# plug-v24-Make-board-myself-to-test-circu.net
KiCad netlist of a schematic drawn in EAGLE
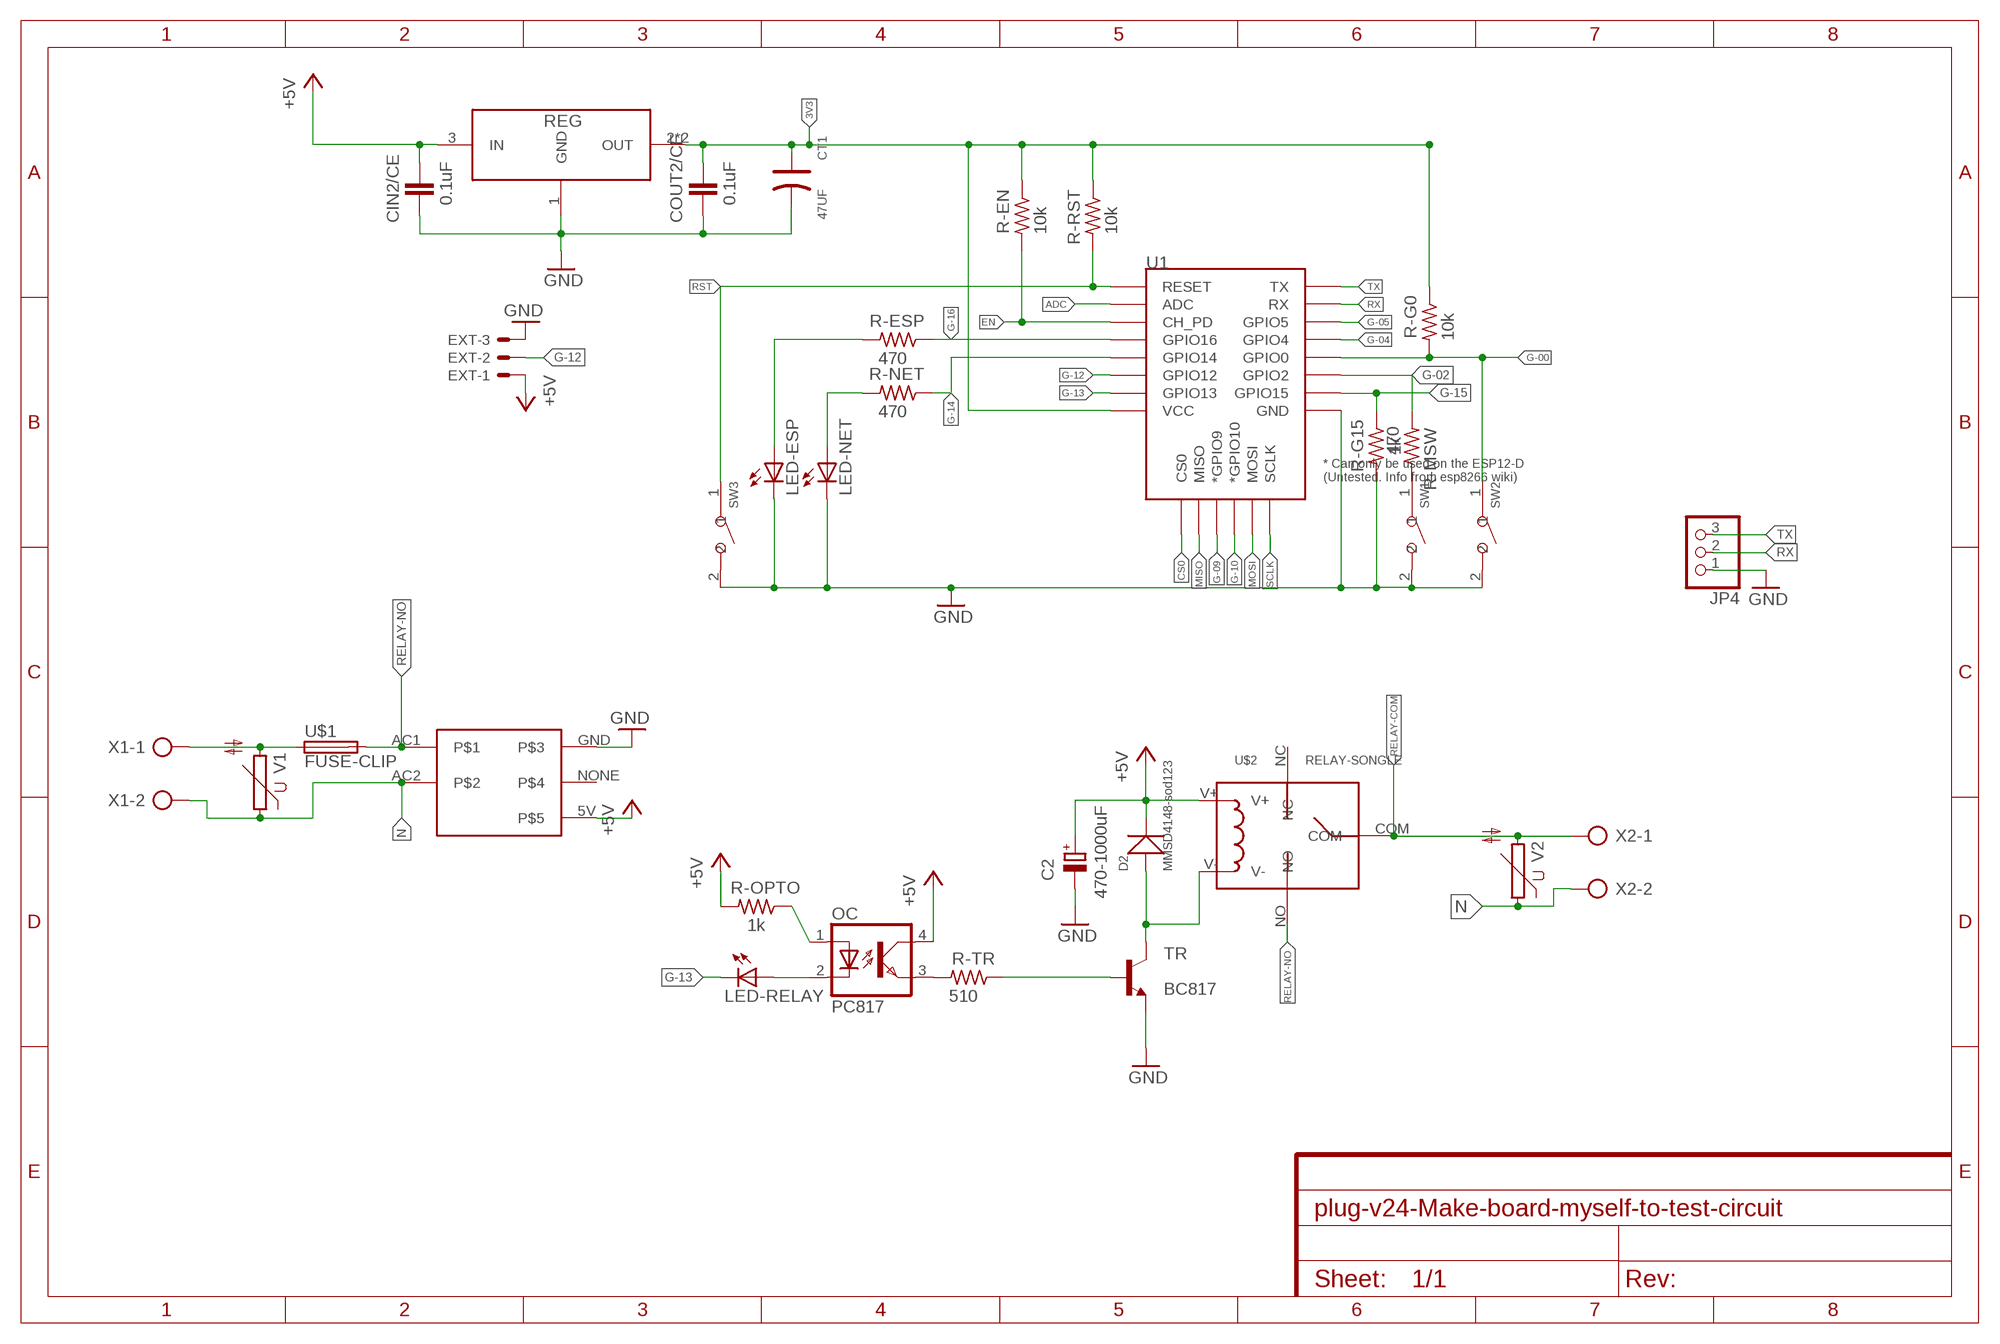
[diagram p0: schematic, sheet 1]

(export (version "E")
  (design (tool "Eeschema 10.0.6"))
  (components
    (comp (ref "C2")
      (value "470-1000uF")
      (footprint "eagle-import:E3,5-8")
      (libsource (lib "eagle-import") (part "CPOL-EUE3.5-8"))
    )
    (comp (ref "CIN2/CE")
      (value "0.1uF")
      (footprint "eagle-import:C0805K")
      (libsource (lib "eagle-import") (part "C-EUC0805K"))
    )
    (comp (ref "COUT2/CE")
      (value "0.1uF")
      (footprint "eagle-import:C0805K")
      (libsource (lib "eagle-import") (part "C-EUC0805K"))
    )
    (comp (ref "CT1")
      (value "47UF")
      (footprint "eagle-import:ELECTRO-SMD-C-6MM")
      (fields (field (name "MPN") "CS1E470M-CRE54"))
      (libsource (lib "eagle-import") (part "ALUMINUM-SMD-47UF-25V(D6.3-H5.3MM)"))
    )
    (comp (ref "D2")
      (value "MMSD4148-sod123")
      (footprint "eagle-import:SOD-123")
      (fields (field (name "MPN") "MMSD4148"))
      (libsource (lib "eagle-import") (part "SMD-DIODE-100V-200MA(SOD-123)"))
    )
    (comp (ref "EXT")
      (value "53048-03")
      (footprint "eagle-import:53048-03")
      (fields (field (name "MF") "WALDOM/MOLEX") (field (name "MPN") "53048-0310"))
      (libsource (lib "eagle-import") (part "53?-03048"))
    )
    (comp (ref "JP4")
      (value "PINHD-1X3")
      (footprint "eagle-import:1X03")
      (libsource (lib "eagle-import") (part "PINHD-1X3"))
    )
    (comp (ref "LED-ESP")
      (value "LEDCHIPLED_0805")
      (footprint "eagle-import:CHIPLED_0805")
      (libsource (lib "eagle-import") (part "LEDCHIPLED_0805"))
    )
    (comp (ref "LED-NET")
      (value "LEDCHIPLED_0805")
      (footprint "eagle-import:CHIPLED_0805")
      (libsource (lib "eagle-import") (part "LEDCHIPLED_0805"))
    )
    (comp (ref "LED-RELAY")
      (value "LEDCHIPLED_0805")
      (footprint "eagle-import:CHIPLED_0805")
      (libsource (lib "eagle-import") (part "LEDCHIPLED_0805"))
    )
    (comp (ref "OC")
      (value "PC817")
      (footprint "eagle-import:DIL04")
      (fields (field (name "MPN") "PC817X4J000F"))
      (libsource (lib "eagle-import") (part "PC817"))
    )
    (comp (ref "R-EN")
      (value "10k")
      (footprint "eagle-import:M0805")
      (libsource (lib "eagle-import") (part "R-US_M0805"))
    )
    (comp (ref "R-ESP")
      (value "470")
      (footprint "eagle-import:M0805")
      (libsource (lib "eagle-import") (part "R-US_M0805"))
    )
    (comp (ref "R-G0")
      (value "10k")
      (footprint "eagle-import:M0805")
      (libsource (lib "eagle-import") (part "R-US_M0805"))
    )
    (comp (ref "R-G15")
      (value "1k")
      (footprint "eagle-import:M0805")
      (libsource (lib "eagle-import") (part "R-US_M0805"))
    )
    (comp (ref "R-MSW")
      (value "470")
      (footprint "eagle-import:M0805")
      (libsource (lib "eagle-import") (part "R-US_M0805"))
    )
    (comp (ref "R-NET")
      (value "470")
      (footprint "eagle-import:M0805")
      (libsource (lib "eagle-import") (part "R-US_M0805"))
    )
    (comp (ref "R-OPTO")
      (value "1k")
      (footprint "eagle-import:M0805")
      (libsource (lib "eagle-import") (part "R-US_M0805"))
    )
    (comp (ref "R-RST")
      (value "10k")
      (footprint "eagle-import:M0805")
      (libsource (lib "eagle-import") (part "R-US_M0805"))
    )
    (comp (ref "R-TR")
      (value "510")
      (footprint "eagle-import:M0805")
      (libsource (lib "eagle-import") (part "R-US_M0805"))
    )
    (comp (ref "REG")
      (value "AMS1117-3.3")
      (footprint "eagle-import:SOT-223")
      (libsource (lib "eagle-import") (part "AMS1117-3.3"))
    )
    (comp (ref "SW1")
      (value "DIP-BUTTON(2P-6.0X3.0X4.3MM)-TS-1101F")
      (footprint "eagle-import:SW2-5.0-6.0X3.0X4.3MM")
      (libsource (lib "eagle-import") (part "DIP-BUTTON(2P-6.0X3.0X4.3MM)-TS-1101F"))
    )
    (comp (ref "SW2")
      (value "DIP-BUTTON(2P-6.0X3.0X4.3MM)-TS-1101F")
      (footprint "eagle-import:SW2-5.0-6.0X3.0X4.3MM")
      (libsource (lib "eagle-import") (part "DIP-BUTTON(2P-6.0X3.0X4.3MM)-TS-1101F"))
    )
    (comp (ref "SW3")
      (value "DIP-BUTTON(2P-6.0X3.0X4.3MM)-TS-1101F")
      (footprint "eagle-import:SW2-5.0-6.0X3.0X4.3MM")
      (libsource (lib "eagle-import") (part "DIP-BUTTON(2P-6.0X3.0X4.3MM)-TS-1101F"))
    )
    (comp (ref "TR")
      (value "BC817")
      (footprint "eagle-import:SOT23-BEC")
      (libsource (lib "eagle-import") (part "BC817SMD-16"))
    )
    (comp (ref "U$1")
      (value "FUSE-CLIP")
      (footprint "eagle-import:FUSE-CLIP")
      (libsource (lib "eagle-import") (part "FUSE-CLIP"))
    )
    (comp (ref "U$2")
      (value "RELAY-SONGLE")
      (footprint "eagle-import:RELAY-SONGLE")
      (libsource (lib "eagle-import") (part "RELAY-SONGLE"))
    )
    (comp (ref "U$4")
      (value "POWERSUPPLY-5V-700MA")
      (footprint "eagle-import:POWERSUPPLY-5V-700MA")
      (libsource (lib "eagle-import") (part "POWERSUPPLY-5V-700MA"))
    )
    (comp (ref "U1")
      (value "ESP12ESMD")
      (footprint "eagle-import:ESP12E-SMD")
      (libsource (lib "eagle-import") (part "ESP12ESMD"))
    )
    (comp (ref "V1")
      (value "S14K11")
      (footprint "eagle-import:S14K11")
      (libsource (lib "eagle-import") (part "S14K11"))
    )
    (comp (ref "V2")
      (value "S14K11")
      (footprint "eagle-import:S14K11")
      (libsource (lib "eagle-import") (part "S14K11"))
    )
    (comp (ref "X1")
      (value "AK300/2")
      (footprint "eagle-import:AK300_2")
      (libsource (lib "eagle-import") (part "AK300/2"))
    )
    (comp (ref "X2")
      (value "AK300/2")
      (footprint "eagle-import:AK300_2")
      (libsource (lib "eagle-import") (part "AK300/2"))
    )
  )
  (nets
    (net (code "1") (name "+5V") (class "Default")
      (node (ref "C2") (pin "+") (pinfunction "+_+") (pintype "passive"))
      (node (ref "CIN2/CE") (pin "1") (pinfunction "1_1") (pintype "passive"))
      (node (ref "D2") (pin "-") (pinfunction "-_-") (pintype "passive"))
      (node (ref "EXT") (pin "1") (pinfunction "S_1") (pintype "passive"))
      (node (ref "OC") (pin "4") (pinfunction "COL_4") (pintype "passive"))
      (node (ref "R-OPTO") (pin "2") (pinfunction "2_2") (pintype "passive"))
      (node (ref "REG") (pin "3") (pinfunction "IN_3") (pintype "input"))
      (node (ref "U$2") (pin "V+") (pinfunction "V+_V+") (pintype "bidirectional"))
      (node (ref "U$4") (pin "5V") (pinfunction "P$5_5V") (pintype "bidirectional"))
    )
    (net (code "2") (name "3V3") (class "Default")
      (node (ref "COUT2/CE") (pin "1") (pinfunction "1_1") (pintype "passive"))
      (node (ref "CT1") (pin "+") (pinfunction "+_+") (pintype "passive"))
      (node (ref "R-EN") (pin "1") (pinfunction "1_1") (pintype "passive"))
      (node (ref "R-G0") (pin "1") (pinfunction "1_1") (pintype "passive"))
      (node (ref "R-RST") (pin "1") (pinfunction "1_1") (pintype "passive"))
      (node (ref "REG") (pin "2") (pinfunction "OUT_2") (pintype "output"))
      (node (ref "REG") (pin "4") (pinfunction "OUT_4") (pintype "output"))
      (node (ref "U1") (pin "VCC") (pinfunction "VCC_VCC") (pintype "bidirectional"))
    )
    (net (code "3") (name "ADC") (class "Default")
      (node (ref "U1") (pin "ADC") (pinfunction "ADC_ADC") (pintype "bidirectional"))
    )
    (net (code "4") (name "CS0") (class "Default")
      (node (ref "U1") (pin "CS0") (pinfunction "CS0_CS0") (pintype "bidirectional"))
    )
    (net (code "5") (name "EN") (class "Default")
      (node (ref "R-EN") (pin "2") (pinfunction "2_2") (pintype "passive"))
      (node (ref "U1") (pin "CH_PD") (pinfunction "CH_PD_CH_PD") (pintype "bidirectional"))
    )
    (net (code "6") (name "G-00") (class "Default")
      (node (ref "R-G0") (pin "2") (pinfunction "2_2") (pintype "passive"))
      (node (ref "SW2") (pin "1") (pinfunction "1_1") (pintype "bidirectional"))
      (node (ref "U1") (pin "GPIO0") (pinfunction "GPIO0_GPIO0") (pintype "bidirectional"))
    )
    (net (code "7") (name "G-02") (class "Default")
      (node (ref "R-MSW") (pin "2") (pinfunction "2_2") (pintype "passive"))
      (node (ref "U1") (pin "GPIO2") (pinfunction "GPIO2_GPIO2") (pintype "bidirectional"))
    )
    (net (code "8") (name "G-04") (class "Default")
      (node (ref "U1") (pin "GPIO4") (pinfunction "GPIO4_GPIO4") (pintype "bidirectional"))
    )
    (net (code "9") (name "G-05") (class "Default")
      (node (ref "U1") (pin "GPIO5") (pinfunction "GPIO5_GPIO5") (pintype "bidirectional"))
    )
    (net (code "10") (name "G-09") (class "Default")
      (node (ref "U1") (pin "GPIO9") (pinfunction "*GPIO9_GPIO9") (pintype "bidirectional"))
    )
    (net (code "11") (name "G-10") (class "Default")
      (node (ref "U1") (pin "GPIO10") (pinfunction "*GPIO10_GPIO10") (pintype "bidirectional"))
    )
    (net (code "12") (name "G-12") (class "Default")
      (node (ref "EXT") (pin "2") (pinfunction "S_2") (pintype "passive"))
      (node (ref "U1") (pin "GPIO12") (pinfunction "GPIO12_GPIO12") (pintype "bidirectional"))
    )
    (net (code "13") (name "G-13") (class "Default")
      (node (ref "LED-RELAY") (pin "C") (pinfunction "C_C") (pintype "passive"))
      (node (ref "U1") (pin "GPIO13") (pinfunction "GPIO13_GPIO13") (pintype "bidirectional"))
    )
    (net (code "14") (name "G-14") (class "Default")
      (node (ref "R-NET") (pin "1") (pinfunction "1_1") (pintype "passive"))
      (node (ref "U1") (pin "GPIO14") (pinfunction "GPIO14_GPIO14") (pintype "bidirectional"))
    )
    (net (code "15") (name "G-15") (class "Default")
      (node (ref "R-G15") (pin "1") (pinfunction "1_1") (pintype "passive"))
      (node (ref "U1") (pin "GPIO15") (pinfunction "GPIO15_GPIO15") (pintype "bidirectional"))
    )
    (net (code "16") (name "G-16") (class "Default")
      (node (ref "R-ESP") (pin "1") (pinfunction "1_1") (pintype "passive"))
      (node (ref "U1") (pin "GPIO16") (pinfunction "GPIO16_GPIO16") (pintype "bidirectional"))
    )
    (net (code "17") (name "GND") (class "Default")
      (node (ref "C2") (pin "-") (pinfunction "-_-") (pintype "passive"))
      (node (ref "CIN2/CE") (pin "2") (pinfunction "2_2") (pintype "passive"))
      (node (ref "COUT2/CE") (pin "2") (pinfunction "2_2") (pintype "passive"))
      (node (ref "CT1") (pin "-") (pinfunction "-_-") (pintype "passive"))
      (node (ref "EXT") (pin "3") (pinfunction "S_3") (pintype "passive"))
      (node (ref "JP4") (pin "1") (pinfunction "1_1") (pintype "passive"))
      (node (ref "LED-ESP") (pin "C") (pinfunction "C_C") (pintype "passive"))
      (node (ref "LED-NET") (pin "C") (pinfunction "C_C") (pintype "passive"))
      (node (ref "R-G15") (pin "2") (pinfunction "2_2") (pintype "passive"))
      (node (ref "REG") (pin "1") (pinfunction "GND_1") (pintype "passive"))
      (node (ref "SW1") (pin "2") (pinfunction "2_2") (pintype "bidirectional"))
      (node (ref "SW2") (pin "2") (pinfunction "2_2") (pintype "bidirectional"))
      (node (ref "SW3") (pin "2") (pinfunction "2_2") (pintype "bidirectional"))
      (node (ref "TR") (pin "E") (pinfunction "E_E") (pintype "passive"))
      (node (ref "U$4") (pin "GND") (pinfunction "P$3_GND") (pintype "bidirectional"))
      (node (ref "U1") (pin "GND") (pinfunction "GND_GND") (pintype "bidirectional"))
    )
    (net (code "18") (name "MISO") (class "Default")
      (node (ref "U1") (pin "MISO") (pinfunction "MISO_MISO") (pintype "bidirectional"))
    )
    (net (code "19") (name "MOSI") (class "Default")
      (node (ref "U1") (pin "MOSI") (pinfunction "MOSI_MOSI") (pintype "bidirectional"))
    )
    (net (code "20") (name "N") (class "Default")
      (node (ref "U$4") (pin "AC2") (pinfunction "P$2_AC2") (pintype "bidirectional"))
      (node (ref "V1") (pin "1") (pinfunction "1_1") (pintype "passive"))
      (node (ref "V2") (pin "1") (pinfunction "1_1") (pintype "passive"))
      (node (ref "X1") (pin "2") (pinfunction "KL_2") (pintype "passive"))
      (node (ref "X2") (pin "2") (pinfunction "KL_2") (pintype "passive"))
    )
    (net (code "21") (name "Net-(D2-Pad+)") (class "Default")
      (node (ref "D2") (pin "+") (pinfunction "+_+") (pintype "passive"))
      (node (ref "TR") (pin "C") (pinfunction "C_C") (pintype "passive"))
      (node (ref "U$2") (pin "V-") (pinfunction "V-_V-") (pintype "bidirectional"))
    )
    (net (code "22") (name "Net-(LED-ESP-PadA)") (class "Default")
      (node (ref "LED-ESP") (pin "A") (pinfunction "A_A") (pintype "passive"))
      (node (ref "R-ESP") (pin "2") (pinfunction "2_2") (pintype "passive"))
    )
    (net (code "23") (name "Net-(LED-NET-PadA)") (class "Default")
      (node (ref "LED-NET") (pin "A") (pinfunction "A_A") (pintype "passive"))
      (node (ref "R-NET") (pin "2") (pinfunction "2_2") (pintype "passive"))
    )
    (net (code "24") (name "Net-(OC-A)") (class "Default")
      (node (ref "OC") (pin "1") (pinfunction "A_1") (pintype "passive"))
      (node (ref "R-OPTO") (pin "1") (pinfunction "1_1") (pintype "passive"))
    )
    (net (code "25") (name "Net-(OC-C)") (class "Default")
      (node (ref "LED-RELAY") (pin "A") (pinfunction "A_A") (pintype "passive"))
      (node (ref "OC") (pin "2") (pinfunction "C_2") (pintype "passive"))
    )
    (net (code "26") (name "Net-(OC-EMIT)") (class "Default")
      (node (ref "OC") (pin "3") (pinfunction "EMIT_3") (pintype "passive"))
      (node (ref "R-TR") (pin "2") (pinfunction "2_2") (pintype "passive"))
    )
    (net (code "27") (name "Net-(R-MSW-Pad1)") (class "Default")
      (node (ref "R-MSW") (pin "1") (pinfunction "1_1") (pintype "passive"))
      (node (ref "SW1") (pin "1") (pinfunction "1_1") (pintype "bidirectional"))
    )
    (net (code "28") (name "Net-(R-TR-Pad1)") (class "Default")
      (node (ref "R-TR") (pin "1") (pinfunction "1_1") (pintype "passive"))
      (node (ref "TR") (pin "B") (pinfunction "B_B") (pintype "passive"))
    )
    (net (code "29") (name "Net-(X1A-KL)") (class "Default")
      (node (ref "U$1") (pin "3") (pinfunction "1_3") (pintype "passive"))
      (node (ref "U$1") (pin "4") (pinfunction "1_4") (pintype "passive"))
      (node (ref "V1") (pin "2") (pinfunction "2_2") (pintype "passive"))
      (node (ref "X1") (pin "1") (pinfunction "KL_1") (pintype "passive"))
    )
    (net (code "30") (name "RELAY-COM") (class "Default")
      (node (ref "U$2") (pin "COM") (pinfunction "COM_COM") (pintype "bidirectional"))
      (node (ref "V2") (pin "2") (pinfunction "2_2") (pintype "passive"))
      (node (ref "X2") (pin "1") (pinfunction "KL_1") (pintype "passive"))
    )
    (net (code "31") (name "RELAY-NO") (class "Default")
      (node (ref "U$1") (pin "5") (pinfunction "2_5") (pintype "passive"))
      (node (ref "U$1") (pin "6") (pinfunction "2_6") (pintype "passive"))
      (node (ref "U$2") (pin "NO") (pinfunction "NO_NO") (pintype "bidirectional"))
      (node (ref "U$4") (pin "AC1") (pinfunction "P$1_AC1") (pintype "bidirectional"))
    )
    (net (code "32") (name "RST") (class "Default")
      (node (ref "R-RST") (pin "2") (pinfunction "2_2") (pintype "passive"))
      (node (ref "SW3") (pin "1") (pinfunction "1_1") (pintype "bidirectional"))
      (node (ref "U1") (pin "RESET") (pinfunction "RESET_RESET") (pintype "bidirectional"))
    )
    (net (code "33") (name "RX") (class "Default")
      (node (ref "JP4") (pin "2") (pinfunction "2_2") (pintype "passive"))
      (node (ref "U1") (pin "RXD0") (pinfunction "RX_RXD0") (pintype "bidirectional"))
    )
    (net (code "34") (name "SCLK") (class "Default")
      (node (ref "U1") (pin "SCLK") (pinfunction "SCLK_SCLK") (pintype "bidirectional"))
    )
    (net (code "35") (name "TX") (class "Default")
      (node (ref "JP4") (pin "3") (pinfunction "3_3") (pintype "passive"))
      (node (ref "U1") (pin "TXD0") (pinfunction "TX_TXD0") (pintype "bidirectional"))
    )
    (net (code "36") (name "unconnected-(U$2-PadNC)") (class "Default")
      (node (ref "U$2") (pin "NC") (pinfunction "NC_NC") (pintype "bidirectional"))
    )
    (net (code "37") (name "unconnected-(U$4-P$4-PadNONE)") (class "Default")
      (node (ref "U$4") (pin "NONE") (pinfunction "P$4_NONE") (pintype "bidirectional"))
    )
  )
)
